# Memory.net
KiCad netlist of a schematic drawn in Altium Designer
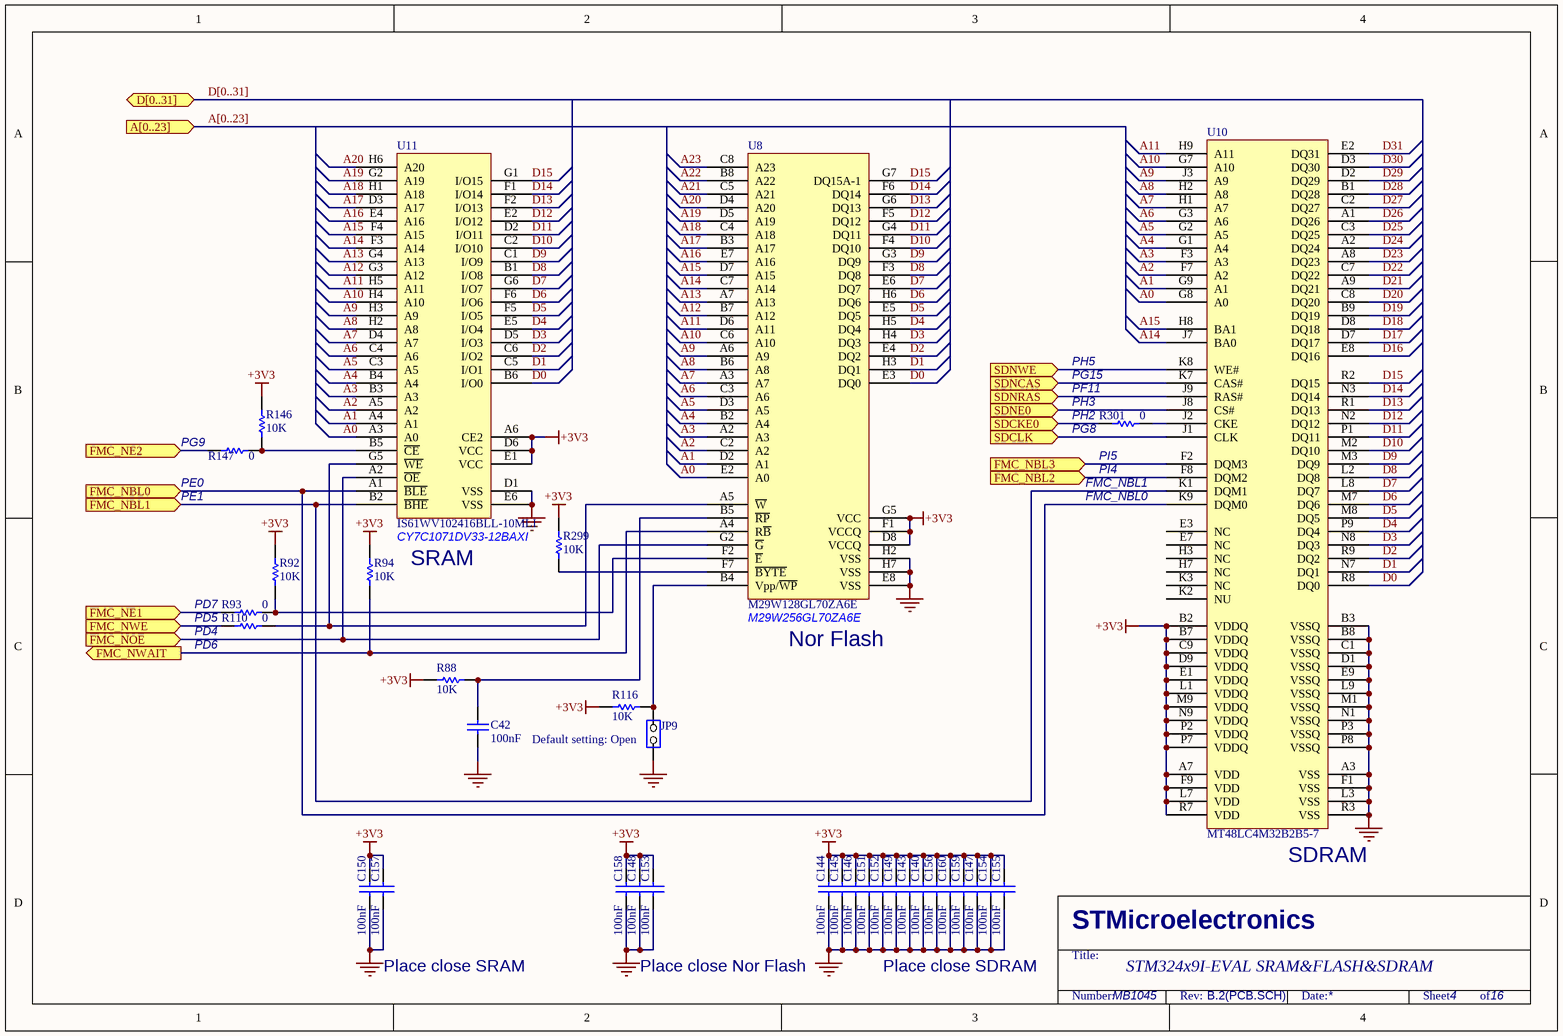
[diagram p0: Memory.SchDoc]

(export (version "E")
  (design (tool "Eeschema 10.0.6"))
  (components
    (comp (ref "C42")
      (value "100nF")
      (footprint "0603C")
      (description "Capacitor")
      (fields (field (name "PUBLISHER") "Altium Limited"))
      (libsource (lib "Miscellaneous Devices") (part "Cap"))
    )
    (comp (ref "C140")
      (value "100nF")
      (footprint "0603C")
      (description "Capacitor")
      (fields (field (name "PUBLISHER") "Altium Limited"))
      (libsource (lib "Miscellaneous Devices") (part "Cap"))
    )
    (comp (ref "C143")
      (value "100nF")
      (footprint "0603C")
      (description "Capacitor")
      (fields (field (name "PUBLISHER") "Altium Limited"))
      (libsource (lib "Miscellaneous Devices") (part "Cap"))
    )
    (comp (ref "C144")
      (value "100nF")
      (footprint "0603C")
      (description "Capacitor")
      (fields (field (name "PUBLISHER") "Altium Limited"))
      (libsource (lib "Miscellaneous Devices") (part "Cap"))
    )
    (comp (ref "C145")
      (value "100nF")
      (footprint "0603C")
      (description "Capacitor")
      (fields (field (name "PUBLISHER") "Altium Limited"))
      (libsource (lib "Miscellaneous Devices") (part "Cap"))
    )
    (comp (ref "C146")
      (value "100nF")
      (footprint "0603C")
      (description "Capacitor")
      (fields (field (name "PUBLISHER") "Altium Limited"))
      (libsource (lib "Miscellaneous Devices") (part "Cap"))
    )
    (comp (ref "C147")
      (value "100nF")
      (footprint "0603C")
      (description "Capacitor")
      (fields (field (name "PUBLISHER") "Altium Limited"))
      (libsource (lib "Miscellaneous Devices") (part "Cap"))
    )
    (comp (ref "C148")
      (value "100nF")
      (footprint "0603C")
      (description "Capacitor")
      (fields (field (name "PUBLISHER") "Altium Limited"))
      (libsource (lib "Miscellaneous Devices") (part "Cap"))
    )
    (comp (ref "C149")
      (value "100nF")
      (footprint "0603C")
      (description "Capacitor")
      (fields (field (name "PUBLISHER") "Altium Limited"))
      (libsource (lib "Miscellaneous Devices") (part "Cap"))
    )
    (comp (ref "C150")
      (value "100nF")
      (footprint "0603C")
      (description "Capacitor")
      (fields (field (name "PUBLISHER") "Altium Limited"))
      (libsource (lib "Miscellaneous Devices") (part "Cap"))
    )
    (comp (ref "C151")
      (value "100nF")
      (footprint "0603C")
      (description "Capacitor")
      (fields (field (name "PUBLISHER") "Altium Limited"))
      (libsource (lib "Miscellaneous Devices") (part "Cap"))
    )
    (comp (ref "C152")
      (value "100nF")
      (footprint "0603C")
      (description "Capacitor")
      (fields (field (name "PUBLISHER") "Altium Limited"))
      (libsource (lib "Miscellaneous Devices") (part "Cap"))
    )
    (comp (ref "C153")
      (value "100nF")
      (footprint "0603C")
      (description "Capacitor")
      (fields (field (name "PUBLISHER") "Altium Limited"))
      (libsource (lib "Miscellaneous Devices") (part "Cap"))
    )
    (comp (ref "C154")
      (value "100nF")
      (footprint "0603C")
      (description "Capacitor")
      (fields (field (name "PUBLISHER") "Altium Limited"))
      (libsource (lib "Miscellaneous Devices") (part "Cap"))
    )
    (comp (ref "C155")
      (value "100nF")
      (footprint "0603C")
      (description "Capacitor")
      (fields (field (name "PUBLISHER") "Altium Limited"))
      (libsource (lib "Miscellaneous Devices") (part "Cap"))
    )
    (comp (ref "C156")
      (value "100nF")
      (footprint "0603C")
      (description "Capacitor")
      (fields (field (name "PUBLISHER") "Altium Limited"))
      (libsource (lib "Miscellaneous Devices") (part "Cap"))
    )
    (comp (ref "C157")
      (value "100nF")
      (footprint "0603C")
      (description "Capacitor")
      (fields (field (name "PUBLISHER") "Altium Limited"))
      (libsource (lib "Miscellaneous Devices") (part "Cap"))
    )
    (comp (ref "C158")
      (value "100nF")
      (footprint "0603C")
      (description "Capacitor")
      (fields (field (name "PUBLISHER") "Altium Limited"))
      (libsource (lib "Miscellaneous Devices") (part "Cap"))
    )
    (comp (ref "C159")
      (value "100nF")
      (footprint "0603C")
      (description "Capacitor")
      (fields (field (name "PUBLISHER") "Altium Limited"))
      (libsource (lib "Miscellaneous Devices") (part "Cap"))
    )
    (comp (ref "C160")
      (value "100nF")
      (footprint "0603C")
      (description "Capacitor")
      (fields (field (name "PUBLISHER") "Altium Limited"))
      (libsource (lib "Miscellaneous Devices") (part "Cap"))
    )
    (comp (ref "JP9") (value "~") (footprint "SIP2") (libsource (lib "*") (part "JP2")))
    (comp (ref "R88")
      (value "10K")
      (footprint "0603R")
      (description "Resistor")
      (fields (field (name "PUBLISHER") "Altium Limited"))
      (libsource (lib "Miscellaneous Devices") (part "Res1"))
    )
    (comp (ref "R92")
      (value "10K")
      (footprint "0603R")
      (description "Resistor")
      (fields (field (name "PUBLISHER") "Altium Limited"))
      (libsource (lib "Miscellaneous Devices") (part "Res1"))
    )
    (comp (ref "R93")
      (value "0")
      (footprint "0603R")
      (description "Resistor")
      (fields (field (name "PUBLISHER") "Altium Limited"))
      (libsource (lib "Miscellaneous Devices") (part "Res1"))
    )
    (comp (ref "R94")
      (value "10K")
      (footprint "0603R")
      (description "Resistor")
      (fields (field (name "PUBLISHER") "Altium Limited"))
      (libsource (lib "Miscellaneous Devices") (part "Res1"))
    )
    (comp (ref "R110")
      (value "0")
      (footprint "0603R")
      (description "Resistor")
      (fields (field (name "PUBLISHER") "Altium Limited"))
      (libsource (lib "Miscellaneous Devices") (part "Res1"))
    )
    (comp (ref "R116")
      (value "10K")
      (footprint "0603R")
      (description "Resistor")
      (fields (field (name "PUBLISHER") "Altium Limited"))
      (libsource (lib "Miscellaneous Devices") (part "Res1"))
    )
    (comp (ref "R146")
      (value "10K")
      (footprint "0603R")
      (description "Resistor")
      (fields (field (name "PUBLISHER") "Altium Limited"))
      (libsource (lib "Miscellaneous Devices") (part "Res1"))
    )
    (comp (ref "R147")
      (value "0")
      (footprint "0603R")
      (description "Resistor")
      (fields (field (name "PUBLISHER") "Altium Limited"))
      (libsource (lib "Miscellaneous Devices") (part "Res1"))
    )
    (comp (ref "R299")
      (value "10K")
      (footprint "0603R")
      (description "Resistor")
      (fields (field (name "PUBLISHER") "Altium Limited"))
      (libsource (lib "Miscellaneous Devices") (part "Res1"))
    )
    (comp (ref "R301")
      (value "0")
      (footprint "0603R")
      (description "Resistor")
      (fields (field (name "PUBLISHER") "Altium Limited"))
      (libsource (lib "Miscellaneous Devices") (part "Res1"))
    )
    (comp (ref "U8")
      (value "M29W128GL70ZA6E")
      (footprint "BGA64_1_10X13")
      (libsource (lib "MB964") (part "M29W128FL70ZA6E"))
    )
    (comp (ref "U10")
      (value "MT48LC4M32B2B5-7")
      (footprint "FBGA90_0R8_8X13")
      (libsource (lib "mb1045") (part "MT48LC4M32B2B5"))
    )
    (comp (ref "U11")
      (value "IS61WV102416BLL-10MLI")
      (footprint "BGA48_0R75_9X11")
      (libsource (lib "MB901") (part "IS61WV102416BLL-10MLI"))
    )
  )
  (nets
    (net (code "1") (name "+3V3") (class "Default")
      (node (ref "C140") (pin "1") (pinfunction "1_1") (pintype "passive"))
      (node (ref "C143") (pin "1") (pinfunction "1_1") (pintype "passive"))
      (node (ref "C144") (pin "1") (pinfunction "1_1") (pintype "passive"))
      (node (ref "C145") (pin "1") (pinfunction "1_1") (pintype "passive"))
      (node (ref "C146") (pin "1") (pinfunction "1_1") (pintype "passive"))
      (node (ref "C147") (pin "1") (pinfunction "1_1") (pintype "passive"))
      (node (ref "C148") (pin "1") (pinfunction "1_1") (pintype "passive"))
      (node (ref "C149") (pin "1") (pinfunction "1_1") (pintype "passive"))
      (node (ref "C150") (pin "1") (pinfunction "1_1") (pintype "passive"))
      (node (ref "C151") (pin "1") (pinfunction "1_1") (pintype "passive"))
      (node (ref "C152") (pin "1") (pinfunction "1_1") (pintype "passive"))
      (node (ref "C153") (pin "1") (pinfunction "1_1") (pintype "passive"))
      (node (ref "C154") (pin "1") (pinfunction "1_1") (pintype "passive"))
      (node (ref "C155") (pin "1") (pinfunction "1_1") (pintype "passive"))
      (node (ref "C156") (pin "1") (pinfunction "1_1") (pintype "passive"))
      (node (ref "C157") (pin "1") (pinfunction "1_1") (pintype "passive"))
      (node (ref "C158") (pin "1") (pinfunction "1_1") (pintype "passive"))
      (node (ref "C159") (pin "1") (pinfunction "1_1") (pintype "passive"))
      (node (ref "C160") (pin "1") (pinfunction "1_1") (pintype "passive"))
      (node (ref "R116") (pin "2") (pinfunction "2_2") (pintype "passive"))
      (node (ref "R146") (pin "2") (pinfunction "2_2") (pintype "passive"))
      (node (ref "R299") (pin "2") (pinfunction "2_2") (pintype "passive"))
      (node (ref "R88") (pin "1") (pinfunction "1_1") (pintype "passive"))
      (node (ref "R92") (pin "2") (pinfunction "2_2") (pintype "passive"))
      (node (ref "R94") (pin "2") (pinfunction "2_2") (pintype "passive"))
      (node (ref "U10") (pin "A7") (pinfunction "VDD_A7") (pintype "passive"))
      (node (ref "U10") (pin "B2") (pinfunction "VDDQ_B2") (pintype "passive"))
      (node (ref "U10") (pin "B7") (pinfunction "VDDQ_B7") (pintype "passive"))
      (node (ref "U10") (pin "C9") (pinfunction "VDDQ_C9") (pintype "passive"))
      (node (ref "U10") (pin "D9") (pinfunction "VDDQ_D9") (pintype "passive"))
      (node (ref "U10") (pin "E1") (pinfunction "VDDQ_E1") (pintype "passive"))
      (node (ref "U10") (pin "F9") (pinfunction "VDD_F9") (pintype "passive"))
      (node (ref "U10") (pin "L1") (pinfunction "VDDQ_L1") (pintype "passive"))
      (node (ref "U10") (pin "L7") (pinfunction "VDD_L7") (pintype "passive"))
      (node (ref "U10") (pin "M9") (pinfunction "VDDQ_M9") (pintype "passive"))
      (node (ref "U10") (pin "N9") (pinfunction "VDDQ_N9") (pintype "passive"))
      (node (ref "U10") (pin "P2") (pinfunction "VDDQ_P2") (pintype "passive"))
      (node (ref "U10") (pin "P7") (pinfunction "VDDQ_P7") (pintype "passive"))
      (node (ref "U10") (pin "R7") (pinfunction "VDD_R7") (pintype "passive"))
      (node (ref "U11") (pin "A6") (pinfunction "CE2_A6") (pintype "passive"))
      (node (ref "U11") (pin "D6") (pinfunction "VCC_D6") (pintype "passive"))
      (node (ref "U11") (pin "E1") (pinfunction "VCC_E1") (pintype "passive"))
      (node (ref "U8") (pin "D8") (pinfunction "VCCQ_D8") (pintype "passive"))
      (node (ref "U8") (pin "F1") (pinfunction "VCCQ_F1") (pintype "passive"))
      (node (ref "U8") (pin "G5") (pinfunction "VCC_G5") (pintype "passive"))
    )
    (net (code "2") (name "/A0") (class "Default")
      (node (ref "U10") (pin "G8") (pinfunction "A0_G8") (pintype "passive"))
      (node (ref "U11") (pin "A3") (pinfunction "A0_A3") (pintype "passive"))
      (node (ref "U8") (pin "E2") (pinfunction "A0_E2") (pintype "passive"))
    )
    (net (code "3") (name "/A1") (class "Default")
      (node (ref "U10") (pin "G9") (pinfunction "A1_G9") (pintype "passive"))
      (node (ref "U11") (pin "A4") (pinfunction "A1_A4") (pintype "passive"))
      (node (ref "U8") (pin "D2") (pinfunction "A1_D2") (pintype "passive"))
    )
    (net (code "4") (name "/A2") (class "Default")
      (node (ref "U10") (pin "F7") (pinfunction "A2_F7") (pintype "passive"))
      (node (ref "U11") (pin "A5") (pinfunction "A2_A5") (pintype "passive"))
      (node (ref "U8") (pin "C2") (pinfunction "A2_C2") (pintype "passive"))
    )
    (net (code "5") (name "/A3") (class "Default")
      (node (ref "U10") (pin "F3") (pinfunction "A3_F3") (pintype "passive"))
      (node (ref "U11") (pin "B3") (pinfunction "A3_B3") (pintype "passive"))
      (node (ref "U8") (pin "A2") (pinfunction "A3_A2") (pintype "passive"))
    )
    (net (code "6") (name "/A4") (class "Default")
      (node (ref "U10") (pin "G1") (pinfunction "A4_G1") (pintype "passive"))
      (node (ref "U11") (pin "B4") (pinfunction "A4_B4") (pintype "passive"))
      (node (ref "U8") (pin "B2") (pinfunction "A4_B2") (pintype "passive"))
    )
    (net (code "7") (name "/A5") (class "Default")
      (node (ref "U10") (pin "G2") (pinfunction "A5_G2") (pintype "passive"))
      (node (ref "U11") (pin "C3") (pinfunction "A5_C3") (pintype "passive"))
      (node (ref "U8") (pin "D3") (pinfunction "A5_D3") (pintype "passive"))
    )
    (net (code "8") (name "/A6") (class "Default")
      (node (ref "U10") (pin "G3") (pinfunction "A6_G3") (pintype "passive"))
      (node (ref "U11") (pin "C4") (pinfunction "A6_C4") (pintype "passive"))
      (node (ref "U8") (pin "C3") (pinfunction "A6_C3") (pintype "passive"))
    )
    (net (code "9") (name "/A7") (class "Default")
      (node (ref "U10") (pin "H1") (pinfunction "A7_H1") (pintype "passive"))
      (node (ref "U11") (pin "D4") (pinfunction "A7_D4") (pintype "passive"))
      (node (ref "U8") (pin "A3") (pinfunction "A7_A3") (pintype "passive"))
    )
    (net (code "10") (name "/A8") (class "Default")
      (node (ref "U10") (pin "H2") (pinfunction "A8_H2") (pintype "passive"))
      (node (ref "U11") (pin "H2") (pinfunction "A8_H2") (pintype "passive"))
      (node (ref "U8") (pin "B6") (pinfunction "A8_B6") (pintype "passive"))
    )
    (net (code "11") (name "/A9") (class "Default")
      (node (ref "U10") (pin "J3") (pinfunction "A9_J3") (pintype "passive"))
      (node (ref "U11") (pin "H3") (pinfunction "A9_H3") (pintype "passive"))
      (node (ref "U8") (pin "A6") (pinfunction "A9_A6") (pintype "passive"))
    )
    (net (code "12") (name "/A10") (class "Default")
      (node (ref "U10") (pin "G7") (pinfunction "A10_G7") (pintype "passive"))
      (node (ref "U11") (pin "H4") (pinfunction "A10_H4") (pintype "passive"))
      (node (ref "U8") (pin "C6") (pinfunction "A10_C6") (pintype "passive"))
    )
    (net (code "13") (name "/A11") (class "Default")
      (node (ref "U10") (pin "H9") (pinfunction "A11_H9") (pintype "passive"))
      (node (ref "U11") (pin "H5") (pinfunction "A11_H5") (pintype "passive"))
      (node (ref "U8") (pin "D6") (pinfunction "A11_D6") (pintype "passive"))
    )
    (net (code "14") (name "/A12") (class "Default")
      (node (ref "U11") (pin "G3") (pinfunction "A12_G3") (pintype "passive"))
      (node (ref "U8") (pin "B7") (pinfunction "A12_B7") (pintype "passive"))
    )
    (net (code "15") (name "/A13") (class "Default")
      (node (ref "U11") (pin "G4") (pinfunction "A13_G4") (pintype "passive"))
      (node (ref "U8") (pin "A7") (pinfunction "A13_A7") (pintype "passive"))
    )
    (net (code "16") (name "/A14") (class "Default")
      (node (ref "U10") (pin "J7") (pinfunction "BA0_J7") (pintype "passive"))
      (node (ref "U11") (pin "F3") (pinfunction "A14_F3") (pintype "passive"))
      (node (ref "U8") (pin "C7") (pinfunction "A14_C7") (pintype "passive"))
    )
    (net (code "17") (name "/A15") (class "Default")
      (node (ref "U10") (pin "H8") (pinfunction "BA1_H8") (pintype "passive"))
      (node (ref "U11") (pin "F4") (pinfunction "A15_F4") (pintype "passive"))
      (node (ref "U8") (pin "D7") (pinfunction "A15_D7") (pintype "passive"))
    )
    (net (code "18") (name "/A16") (class "Default")
      (node (ref "U11") (pin "E4") (pinfunction "A16_E4") (pintype "passive"))
      (node (ref "U8") (pin "E7") (pinfunction "A16_E7") (pintype "passive"))
    )
    (net (code "19") (name "/A17") (class "Default")
      (node (ref "U11") (pin "D3") (pinfunction "A17_D3") (pintype "passive"))
      (node (ref "U8") (pin "B3") (pinfunction "A17_B3") (pintype "passive"))
    )
    (net (code "20") (name "/A18") (class "Default")
      (node (ref "U11") (pin "H1") (pinfunction "A18_H1") (pintype "passive"))
      (node (ref "U8") (pin "C4") (pinfunction "A18_C4") (pintype "passive"))
    )
    (net (code "21") (name "/A19") (class "Default")
      (node (ref "U11") (pin "G2") (pinfunction "A19_G2") (pintype "passive"))
      (node (ref "U8") (pin "D5") (pinfunction "A19_D5") (pintype "passive"))
    )
    (net (code "22") (name "/A20") (class "Default")
      (node (ref "U11") (pin "H6") (pinfunction "A20_H6") (pintype "passive"))
      (node (ref "U8") (pin "D4") (pinfunction "A20_D4") (pintype "passive"))
    )
    (net (code "23") (name "/A21") (class "Default")
      (node (ref "U8") (pin "C5") (pinfunction "A21_C5") (pintype "passive"))
    )
    (net (code "24") (name "/A22") (class "Default")
      (node (ref "U8") (pin "B8") (pinfunction "A22_B8") (pintype "passive"))
    )
    (net (code "25") (name "/A23") (class "Default")
      (node (ref "U8") (pin "C8") (pinfunction "A23_C8") (pintype "passive"))
    )
    (net (code "27") (name "/D0") (class "Default")
      (node (ref "U10") (pin "R8") (pinfunction "DQ0_R8") (pintype "passive"))
      (node (ref "U11") (pin "B6") (pinfunction "I/O0_B6") (pintype "passive"))
      (node (ref "U8") (pin "E3") (pinfunction "DQ0_E3") (pintype "passive"))
    )
    (net (code "28") (name "/D1") (class "Default")
      (node (ref "U10") (pin "N7") (pinfunction "DQ1_N7") (pintype "passive"))
      (node (ref "U11") (pin "C5") (pinfunction "I/O1_C5") (pintype "passive"))
      (node (ref "U8") (pin "H3") (pinfunction "DQ1_H3") (pintype "passive"))
    )
    (net (code "29") (name "/D2") (class "Default")
      (node (ref "U10") (pin "R9") (pinfunction "DQ2_R9") (pintype "passive"))
      (node (ref "U11") (pin "C6") (pinfunction "I/O2_C6") (pintype "passive"))
      (node (ref "U8") (pin "E4") (pinfunction "DQ2_E4") (pintype "passive"))
    )
    (net (code "30") (name "/D3") (class "Default")
      (node (ref "U10") (pin "N8") (pinfunction "DQ3_N8") (pintype "passive"))
      (node (ref "U11") (pin "D5") (pinfunction "I/O3_D5") (pintype "passive"))
      (node (ref "U8") (pin "H4") (pinfunction "DQ3_H4") (pintype "passive"))
    )
    (net (code "31") (name "/D4") (class "Default")
      (node (ref "U10") (pin "P9") (pinfunction "DQ4_P9") (pintype "passive"))
      (node (ref "U11") (pin "E5") (pinfunction "I/O4_E5") (pintype "passive"))
      (node (ref "U8") (pin "H5") (pinfunction "DQ4_H5") (pintype "passive"))
    )
    (net (code "32") (name "/D5") (class "Default")
      (node (ref "U10") (pin "M8") (pinfunction "DQ5_M8") (pintype "passive"))
      (node (ref "U11") (pin "F5") (pinfunction "I/O5_F5") (pintype "passive"))
      (node (ref "U8") (pin "E5") (pinfunction "DQ5_E5") (pintype "passive"))
    )
    (net (code "33") (name "/D6") (class "Default")
      (node (ref "U10") (pin "M7") (pinfunction "DQ6_M7") (pintype "passive"))
      (node (ref "U11") (pin "F6") (pinfunction "I/O6_F6") (pintype "passive"))
      (node (ref "U8") (pin "H6") (pinfunction "DQ6_H6") (pintype "passive"))
    )
    (net (code "34") (name "/D7") (class "Default")
      (node (ref "U10") (pin "L8") (pinfunction "DQ7_L8") (pintype "passive"))
      (node (ref "U11") (pin "G6") (pinfunction "I/O7_G6") (pintype "passive"))
      (node (ref "U8") (pin "E6") (pinfunction "DQ7_E6") (pintype "passive"))
    )
    (net (code "35") (name "/D8") (class "Default")
      (node (ref "U10") (pin "L2") (pinfunction "DQ8_L2") (pintype "passive"))
      (node (ref "U11") (pin "B1") (pinfunction "I/O8_B1") (pintype "passive"))
      (node (ref "U8") (pin "F3") (pinfunction "DQ8_F3") (pintype "passive"))
    )
    (net (code "36") (name "/D9") (class "Default")
      (node (ref "U10") (pin "M3") (pinfunction "DQ9_M3") (pintype "passive"))
      (node (ref "U11") (pin "C1") (pinfunction "I/O9_C1") (pintype "passive"))
      (node (ref "U8") (pin "G3") (pinfunction "DQ9_G3") (pintype "passive"))
    )
    (net (code "37") (name "/D10") (class "Default")
      (node (ref "U10") (pin "M2") (pinfunction "DQ10_M2") (pintype "passive"))
      (node (ref "U11") (pin "C2") (pinfunction "I/O10_C2") (pintype "passive"))
      (node (ref "U8") (pin "F4") (pinfunction "DQ10_F4") (pintype "passive"))
    )
    (net (code "38") (name "/D11") (class "Default")
      (node (ref "U10") (pin "P1") (pinfunction "DQ11_P1") (pintype "passive"))
      (node (ref "U11") (pin "D2") (pinfunction "I/O11_D2") (pintype "passive"))
      (node (ref "U8") (pin "G4") (pinfunction "DQ11_G4") (pintype "passive"))
    )
    (net (code "39") (name "/D12") (class "Default")
      (node (ref "U10") (pin "N2") (pinfunction "DQ12_N2") (pintype "passive"))
      (node (ref "U11") (pin "E2") (pinfunction "I/O12_E2") (pintype "passive"))
      (node (ref "U8") (pin "F5") (pinfunction "DQ12_F5") (pintype "passive"))
    )
    (net (code "40") (name "/D13") (class "Default")
      (node (ref "U10") (pin "R1") (pinfunction "DQ13_R1") (pintype "passive"))
      (node (ref "U11") (pin "F2") (pinfunction "I/O13_F2") (pintype "passive"))
      (node (ref "U8") (pin "G6") (pinfunction "DQ13_G6") (pintype "passive"))
    )
    (net (code "41") (name "/D14") (class "Default")
      (node (ref "U10") (pin "N3") (pinfunction "DQ14_N3") (pintype "passive"))
      (node (ref "U11") (pin "F1") (pinfunction "I/O14_F1") (pintype "passive"))
      (node (ref "U8") (pin "F6") (pinfunction "DQ14_F6") (pintype "passive"))
    )
    (net (code "42") (name "/D15") (class "Default")
      (node (ref "U10") (pin "R2") (pinfunction "DQ15_R2") (pintype "passive"))
      (node (ref "U11") (pin "G1") (pinfunction "I/O15_G1") (pintype "passive"))
      (node (ref "U8") (pin "G7") (pinfunction "DQ15A-1_G7") (pintype "passive"))
    )
    (net (code "43") (name "/D16") (class "Default")
      (node (ref "U10") (pin "E8") (pinfunction "DQ16_E8") (pintype "passive"))
    )
    (net (code "44") (name "/D17") (class "Default")
      (node (ref "U10") (pin "D7") (pinfunction "DQ17_D7") (pintype "passive"))
    )
    (net (code "45") (name "/D18") (class "Default")
      (node (ref "U10") (pin "D8") (pinfunction "DQ18_D8") (pintype "passive"))
    )
    (net (code "46") (name "/D19") (class "Default")
      (node (ref "U10") (pin "B9") (pinfunction "DQ19_B9") (pintype "passive"))
    )
    (net (code "47") (name "/D20") (class "Default")
      (node (ref "U10") (pin "C8") (pinfunction "DQ20_C8") (pintype "passive"))
    )
    (net (code "48") (name "/D21") (class "Default")
      (node (ref "U10") (pin "A9") (pinfunction "DQ21_A9") (pintype "passive"))
    )
    (net (code "49") (name "/D22") (class "Default")
      (node (ref "U10") (pin "C7") (pinfunction "DQ22_C7") (pintype "passive"))
    )
    (net (code "50") (name "/D23") (class "Default")
      (node (ref "U10") (pin "A8") (pinfunction "DQ23_A8") (pintype "passive"))
    )
    (net (code "51") (name "/D24") (class "Default")
      (node (ref "U10") (pin "A2") (pinfunction "DQ24_A2") (pintype "passive"))
    )
    (net (code "52") (name "/D25") (class "Default")
      (node (ref "U10") (pin "C3") (pinfunction "DQ25_C3") (pintype "passive"))
    )
    (net (code "53") (name "/D26") (class "Default")
      (node (ref "U10") (pin "A1") (pinfunction "DQ26_A1") (pintype "passive"))
    )
    (net (code "54") (name "/D27") (class "Default")
      (node (ref "U10") (pin "C2") (pinfunction "DQ27_C2") (pintype "passive"))
    )
    (net (code "55") (name "/D28") (class "Default")
      (node (ref "U10") (pin "B1") (pinfunction "DQ28_B1") (pintype "passive"))
    )
    (net (code "56") (name "/D29") (class "Default")
      (node (ref "U10") (pin "D2") (pinfunction "DQ29_D2") (pintype "passive"))
    )
    (net (code "57") (name "/D30") (class "Default")
      (node (ref "U10") (pin "D3") (pinfunction "DQ30_D3") (pintype "passive"))
    )
    (net (code "58") (name "/D31") (class "Default")
      (node (ref "U10") (pin "E2") (pinfunction "DQ31_E2") (pintype "passive"))
    )
    (net (code "60") (name "/FMC_NBL0") (class "Default")
      (node (ref "U10") (pin "K9") (pinfunction "DQM0_K9") (pintype "passive"))
      (node (ref "U11") (pin "A1") (pinfunction "~{BLE}_A1") (pintype "passive"))
    )
    (net (code "61") (name "/FMC_NBL1") (class "Default")
      (node (ref "U10") (pin "K1") (pinfunction "DQM1_K1") (pintype "passive"))
      (node (ref "U11") (pin "B2") (pinfunction "~{BHE}_B2") (pintype "passive"))
    )
    (net (code "62") (name "/FMC_NBL2") (class "Default")
      (node (ref "U10") (pin "F8") (pinfunction "DQM2_F8") (pintype "passive"))
    )
    (net (code "63") (name "/FMC_NBL3") (class "Default")
      (node (ref "U10") (pin "F2") (pinfunction "DQM3_F2") (pintype "passive"))
    )
    (net (code "64") (name "/FMC_NE1") (class "Default")
      (node (ref "R93") (pin "2") (pinfunction "2_2") (pintype "passive"))
    )
    (net (code "65") (name "/FMC_NE2") (class "Default")
      (node (ref "R147") (pin "2") (pinfunction "2_2") (pintype "passive"))
    )
    (net (code "66") (name "/FMC_NOE") (class "Default")
      (node (ref "U11") (pin "A2") (pinfunction "~{OE}_A2") (pintype "passive"))
      (node (ref "U8") (pin "G2") (pinfunction "~{G}_G2") (pintype "passive"))
    )
    (net (code "67") (name "/FMC_NWAIT") (class "Default")
      (node (ref "R94") (pin "1") (pinfunction "1_1") (pintype "passive"))
      (node (ref "U8") (pin "A4") (pinfunction "R~{B}_A4") (pintype "passive"))
    )
    (net (code "68") (name "/FMC_NWE") (class "Default")
      (node (ref "R110") (pin "2") (pinfunction "2_2") (pintype "passive"))
    )
    (net (code "69") (name "/SDCKE0") (class "Default")
      (node (ref "R301") (pin "2") (pinfunction "2_2") (pintype "passive"))
    )
    (net (code "70") (name "/SDCLK") (class "Default")
      (node (ref "U10") (pin "J1") (pinfunction "CLK_J1") (pintype "passive"))
    )
    (net (code "71") (name "/SDNCAS") (class "Default")
      (node (ref "U10") (pin "K7") (pinfunction "CAS#_K7") (pintype "passive"))
    )
    (net (code "72") (name "/SDNE0") (class "Default")
      (node (ref "U10") (pin "J8") (pinfunction "CS#_J8") (pintype "passive"))
    )
    (net (code "73") (name "/SDNRAS") (class "Default")
      (node (ref "U10") (pin "J9") (pinfunction "RAS#_J9") (pintype "passive"))
    )
    (net (code "74") (name "/SDNWE") (class "Default")
      (node (ref "U10") (pin "K8") (pinfunction "WE#_K8") (pintype "passive"))
    )
    (net (code "75") (name "GND") (class "Default")
      (node (ref "C140") (pin "2") (pinfunction "2_2") (pintype "passive"))
      (node (ref "C143") (pin "2") (pinfunction "2_2") (pintype "passive"))
      (node (ref "C144") (pin "2") (pinfunction "2_2") (pintype "passive"))
      (node (ref "C145") (pin "2") (pinfunction "2_2") (pintype "passive"))
      (node (ref "C146") (pin "2") (pinfunction "2_2") (pintype "passive"))
      (node (ref "C147") (pin "2") (pinfunction "2_2") (pintype "passive"))
      (node (ref "C148") (pin "2") (pinfunction "2_2") (pintype "passive"))
      (node (ref "C149") (pin "2") (pinfunction "2_2") (pintype "passive"))
      (node (ref "C150") (pin "2") (pinfunction "2_2") (pintype "passive"))
      (node (ref "C151") (pin "2") (pinfunction "2_2") (pintype "passive"))
      (node (ref "C152") (pin "2") (pinfunction "2_2") (pintype "passive"))
      (node (ref "C153") (pin "2") (pinfunction "2_2") (pintype "passive"))
      (node (ref "C154") (pin "2") (pinfunction "2_2") (pintype "passive"))
      (node (ref "C155") (pin "2") (pinfunction "2_2") (pintype "passive"))
      (node (ref "C156") (pin "2") (pinfunction "2_2") (pintype "passive"))
      (node (ref "C157") (pin "2") (pinfunction "2_2") (pintype "passive"))
      (node (ref "C158") (pin "2") (pinfunction "2_2") (pintype "passive"))
      (node (ref "C159") (pin "2") (pinfunction "2_2") (pintype "passive"))
      (node (ref "C160") (pin "2") (pinfunction "2_2") (pintype "passive"))
      (node (ref "C42") (pin "2") (pinfunction "2_2") (pintype "passive"))
      (node (ref "JP9") (pin "1") (pinfunction "COMMON_1") (pintype "passive"))
      (node (ref "U10") (pin "A3") (pinfunction "VSS_A3") (pintype "passive"))
      (node (ref "U10") (pin "B3") (pinfunction "VSSQ_B3") (pintype "passive"))
      (node (ref "U10") (pin "B8") (pinfunction "VSSQ_B8") (pintype "passive"))
      (node (ref "U10") (pin "C1") (pinfunction "VSSQ_C1") (pintype "passive"))
      (node (ref "U10") (pin "D1") (pinfunction "VSSQ_D1") (pintype "passive"))
      (node (ref "U10") (pin "E9") (pinfunction "VSSQ_E9") (pintype "passive"))
      (node (ref "U10") (pin "F1") (pinfunction "VSS_F1") (pintype "passive"))
      (node (ref "U10") (pin "L3") (pinfunction "VSS_L3") (pintype "passive"))
      (node (ref "U10") (pin "L9") (pinfunction "VSSQ_L9") (pintype "passive"))
      (node (ref "U10") (pin "M1") (pinfunction "VSSQ_M1") (pintype "passive"))
      (node (ref "U10") (pin "N1") (pinfunction "VSSQ_N1") (pintype "passive"))
      (node (ref "U10") (pin "P3") (pinfunction "VSSQ_P3") (pintype "passive"))
      (node (ref "U10") (pin "P8") (pinfunction "VSSQ_P8") (pintype "passive"))
      (node (ref "U10") (pin "R3") (pinfunction "VSS_R3") (pintype "passive"))
      (node (ref "U11") (pin "D1") (pinfunction "VSS_D1") (pintype "passive"))
      (node (ref "U11") (pin "E6") (pinfunction "VSS_E6") (pintype "passive"))
      (node (ref "U8") (pin "E8") (pinfunction "VSS_E8") (pintype "passive"))
      (node (ref "U8") (pin "H2") (pinfunction "VSS_H2") (pintype "passive"))
      (node (ref "U8") (pin "H7") (pinfunction "VSS_H7") (pintype "passive"))
    )
    (net (code "76") (name "Net-(JP9-NO)") (class "Default")
      (node (ref "JP9") (pin "2") (pinfunction "NO_2") (pintype "passive"))
      (node (ref "R116") (pin "1") (pinfunction "1_1") (pintype "passive"))
      (node (ref "U8") (pin "B4") (pinfunction "Vpp/~{WP}_B4") (pintype "passive"))
    )
    (net (code "77") (name "Net-(U8-~{BYTE})") (class "Default")
      (node (ref "R299") (pin "1") (pinfunction "1_1") (pintype "passive"))
      (node (ref "U8") (pin "F7") (pinfunction "~{BYTE}_F7") (pintype "passive"))
    )
    (net (code "78") (name "Net-(U8-~{E})") (class "Default")
      (node (ref "R92") (pin "1") (pinfunction "1_1") (pintype "passive"))
      (node (ref "R93") (pin "1") (pinfunction "1_1") (pintype "passive"))
      (node (ref "U8") (pin "F2") (pinfunction "~{E}_F2") (pintype "passive"))
    )
    (net (code "79") (name "Net-(U8-~{RP})") (class "Default")
      (node (ref "C42") (pin "1") (pinfunction "1_1") (pintype "passive"))
      (node (ref "R88") (pin "2") (pinfunction "2_2") (pintype "passive"))
      (node (ref "U8") (pin "B5") (pinfunction "~{RP}_B5") (pintype "passive"))
    )
    (net (code "80") (name "Net-(U10-CKE)") (class "Default")
      (node (ref "R301") (pin "1") (pinfunction "1_1") (pintype "passive"))
      (node (ref "U10") (pin "J2") (pinfunction "CKE_J2") (pintype "passive"))
    )
    (net (code "81") (name "Net-(U11-~{CE})") (class "Default")
      (node (ref "R146") (pin "1") (pinfunction "1_1") (pintype "passive"))
      (node (ref "R147") (pin "1") (pinfunction "1_1") (pintype "passive"))
      (node (ref "U11") (pin "B5") (pinfunction "~{CE}_B5") (pintype "passive"))
    )
    (net (code "82") (name "Net-(U11-~{WE})") (class "Default")
      (node (ref "R110") (pin "1") (pinfunction "1_1") (pintype "passive"))
      (node (ref "U11") (pin "G5") (pinfunction "~{WE}_G5") (pintype "passive"))
      (node (ref "U8") (pin "A5") (pinfunction "~{W}_A5") (pintype "passive"))
    )
    (net (code "83") (name "unconnected-(U10-NC-PadE3)") (class "Default")
      (node (ref "U10") (pin "E3") (pinfunction "NC_E3") (pintype "passive"))
    )
    (net (code "84") (name "unconnected-(U10-NC-PadE7)") (class "Default")
      (node (ref "U10") (pin "E7") (pinfunction "NC_E7") (pintype "passive"))
    )
    (net (code "85") (name "unconnected-(U10-NC-PadH3)") (class "Default")
      (node (ref "U10") (pin "H3") (pinfunction "NC_H3") (pintype "passive"))
    )
    (net (code "86") (name "unconnected-(U10-NC-PadH7)") (class "Default")
      (node (ref "U10") (pin "H7") (pinfunction "NC_H7") (pintype "passive"))
    )
    (net (code "87") (name "unconnected-(U10-NC-PadK3)") (class "Default")
      (node (ref "U10") (pin "K3") (pinfunction "NC_K3") (pintype "passive"))
    )
    (net (code "88") (name "unconnected-(U10-NU-PadK2)") (class "Default")
      (node (ref "U10") (pin "K2") (pinfunction "NU_K2") (pintype "passive"))
    )
  )
)
